# schematic.net
KiCad netlist of a schematic drawn in Altium Designer
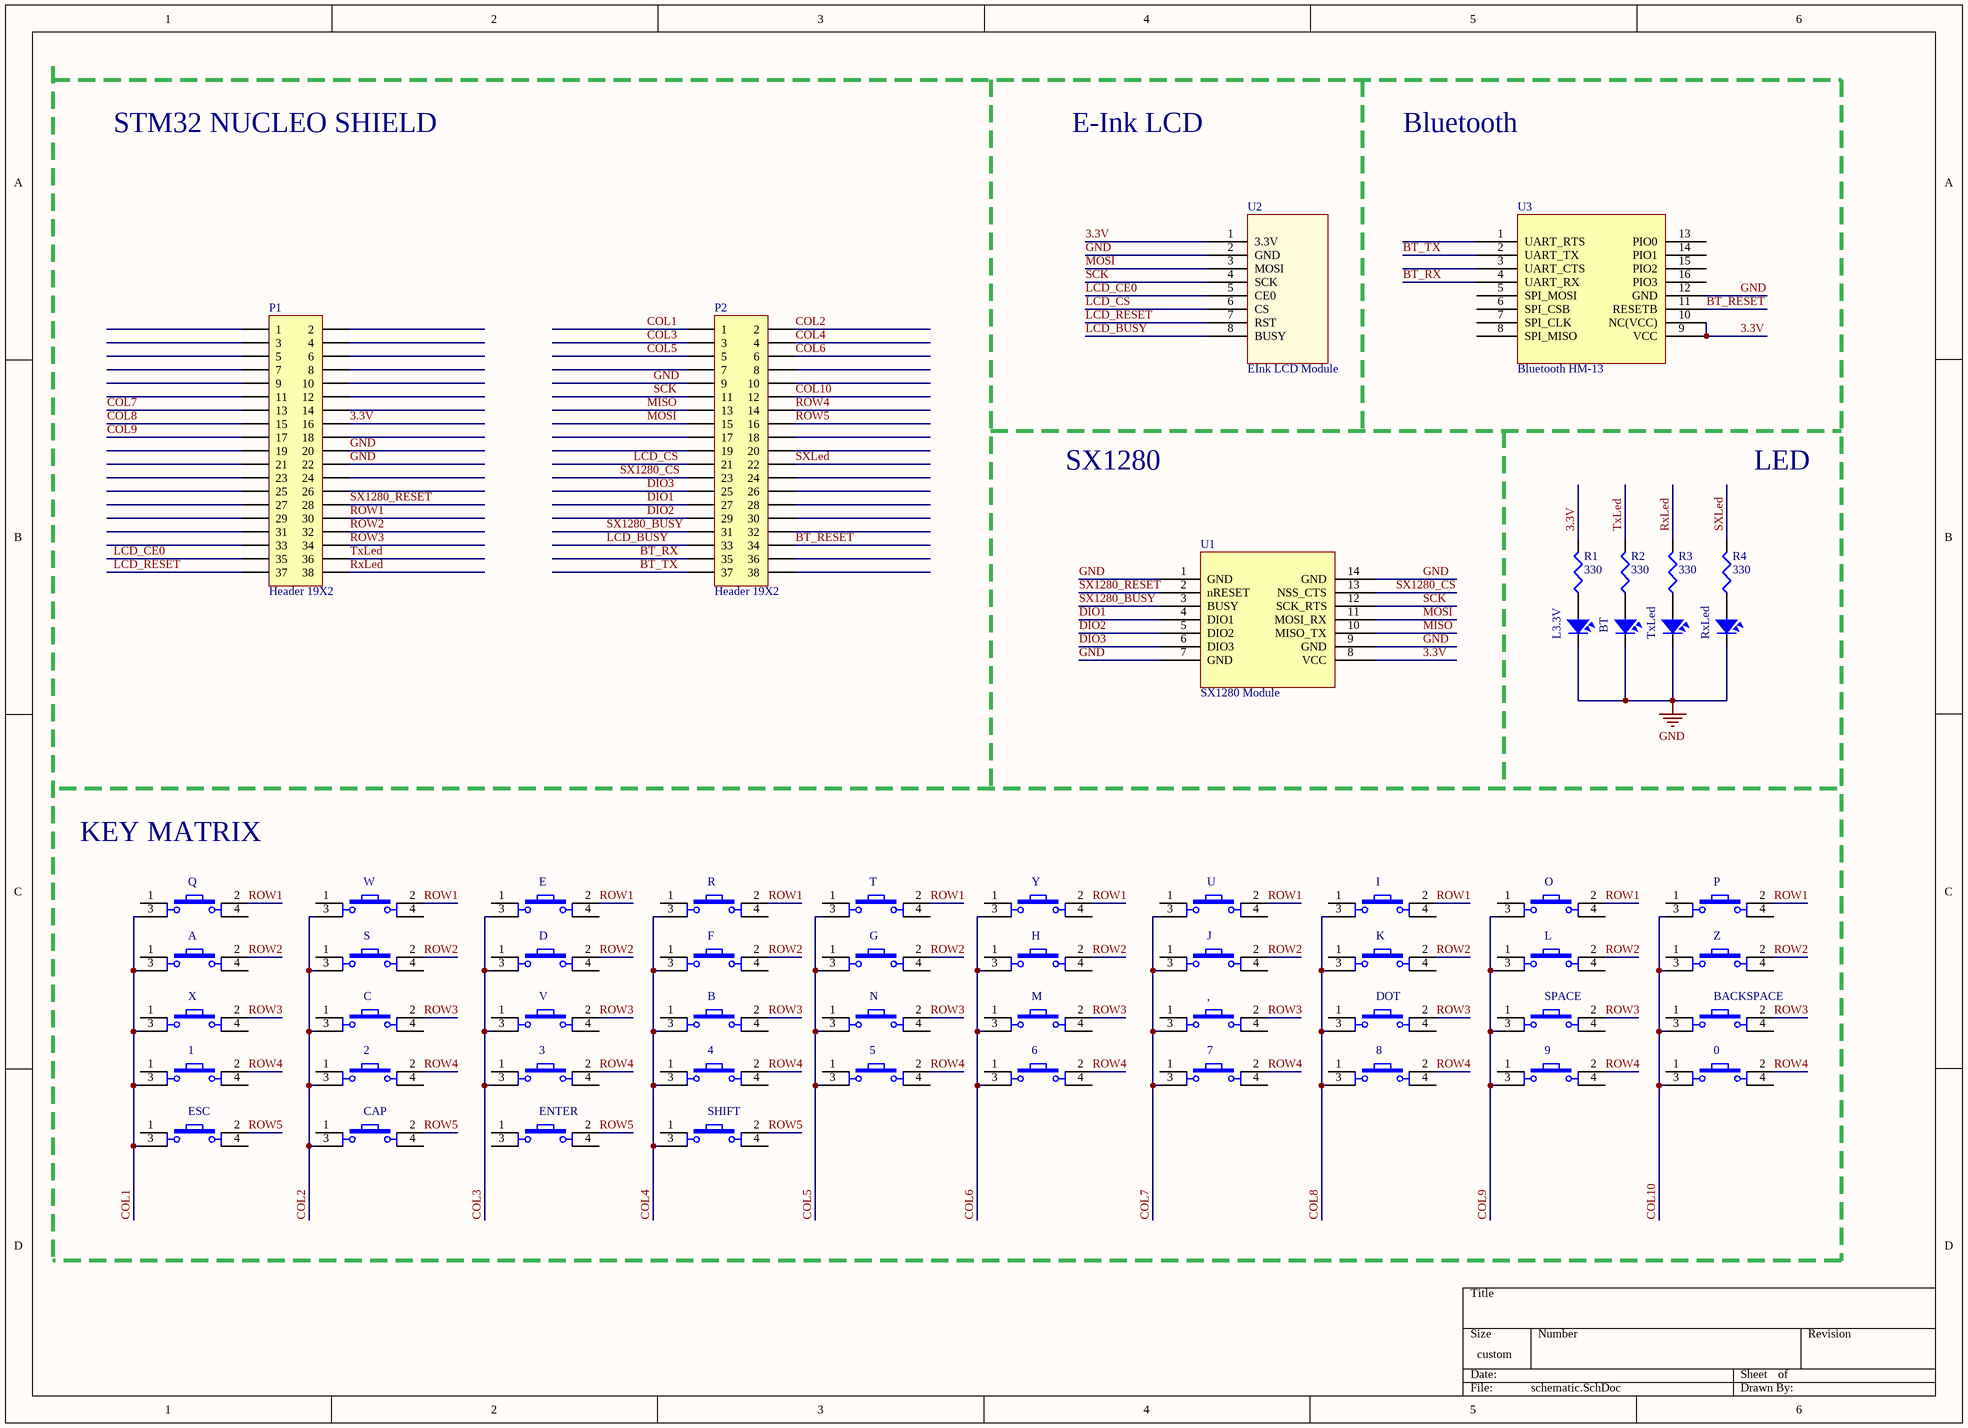
[diagram p0: schematic.SchDoc]

(export (version "E")
  (design (tool "Eeschema 10.0.6"))
  (components
    (comp (ref ",")
      (value "SW")
      (footprint "Button 4 pins")
      (description "Switch button 4 pin")
      (libsource (lib "syhaunguyen") (part "SW4"))
    )
    (comp (ref "0")
      (value "SW")
      (footprint "Button 4 pins")
      (description "Switch button 4 pin")
      (libsource (lib "syhaunguyen") (part "SW4"))
    )
    (comp (ref "1")
      (value "SW")
      (footprint "Button 4 pins")
      (description "Switch button 4 pin")
      (libsource (lib "syhaunguyen") (part "SW4"))
    )
    (comp (ref "2")
      (value "SW")
      (footprint "Button 4 pins")
      (description "Switch button 4 pin")
      (libsource (lib "syhaunguyen") (part "SW4"))
    )
    (comp (ref "3")
      (value "SW")
      (footprint "Button 4 pins")
      (description "Switch button 4 pin")
      (libsource (lib "syhaunguyen") (part "SW4"))
    )
    (comp (ref "4")
      (value "SW")
      (footprint "Button 4 pins")
      (description "Switch button 4 pin")
      (libsource (lib "syhaunguyen") (part "SW4"))
    )
    (comp (ref "5")
      (value "SW")
      (footprint "Button 4 pins")
      (description "Switch button 4 pin")
      (libsource (lib "syhaunguyen") (part "SW4"))
    )
    (comp (ref "6")
      (value "SW")
      (footprint "Button 4 pins")
      (description "Switch button 4 pin")
      (libsource (lib "syhaunguyen") (part "SW4"))
    )
    (comp (ref "7")
      (value "SW")
      (footprint "Button 4 pins")
      (description "Switch button 4 pin")
      (libsource (lib "syhaunguyen") (part "SW4"))
    )
    (comp (ref "8")
      (value "SW")
      (footprint "Button 4 pins")
      (description "Switch button 4 pin")
      (libsource (lib "syhaunguyen") (part "SW4"))
    )
    (comp (ref "9")
      (value "SW")
      (footprint "Button 4 pins")
      (description "Switch button 4 pin")
      (libsource (lib "syhaunguyen") (part "SW4"))
    )
    (comp (ref "A")
      (value "SW")
      (footprint "Button 4 pins")
      (description "Switch button 4 pin")
      (libsource (lib "syhaunguyen") (part "SW4"))
    )
    (comp (ref "B")
      (value "SW")
      (footprint "Button 4 pins")
      (description "Switch button 4 pin")
      (libsource (lib "syhaunguyen") (part "SW4"))
    )
    (comp (ref "BACKSPACE")
      (value "SW")
      (footprint "Button 4 pins")
      (description "Switch button 4 pin")
      (libsource (lib "syhaunguyen") (part "SW4"))
    )
    (comp (ref "BT")
      (value "LED SMD")
      (footprint "SM-LED-0805-Blue")
      (libsource (lib "syhaunguyen") (part "LED-SMD-0805"))
    )
    (comp (ref "C")
      (value "SW")
      (footprint "Button 4 pins")
      (description "Switch button 4 pin")
      (libsource (lib "syhaunguyen") (part "SW4"))
    )
    (comp (ref "CAP")
      (value "SW")
      (footprint "Button 4 pins")
      (description "Switch button 4 pin")
      (libsource (lib "syhaunguyen") (part "SW4"))
    )
    (comp (ref "D")
      (value "SW")
      (footprint "Button 4 pins")
      (description "Switch button 4 pin")
      (libsource (lib "syhaunguyen") (part "SW4"))
    )
    (comp (ref "DOT")
      (value "SW")
      (footprint "Button 4 pins")
      (description "Switch button 4 pin")
      (libsource (lib "syhaunguyen") (part "SW4"))
    )
    (comp (ref "E")
      (value "SW")
      (footprint "Button 4 pins")
      (description "Switch button 4 pin")
      (libsource (lib "syhaunguyen") (part "SW4"))
    )
    (comp (ref "ENTER")
      (value "SW")
      (footprint "Button 4 pins")
      (description "Switch button 4 pin")
      (libsource (lib "syhaunguyen") (part "SW4"))
    )
    (comp (ref "ESC")
      (value "SW")
      (footprint "Button 4 pins")
      (description "Switch button 4 pin")
      (libsource (lib "syhaunguyen") (part "SW4"))
    )
    (comp (ref "F")
      (value "SW")
      (footprint "Button 4 pins")
      (description "Switch button 4 pin")
      (libsource (lib "syhaunguyen") (part "SW4"))
    )
    (comp (ref "G")
      (value "SW")
      (footprint "Button 4 pins")
      (description "Switch button 4 pin")
      (libsource (lib "syhaunguyen") (part "SW4"))
    )
    (comp (ref "H")
      (value "SW")
      (footprint "Button 4 pins")
      (description "Switch button 4 pin")
      (libsource (lib "syhaunguyen") (part "SW4"))
    )
    (comp (ref "I")
      (value "SW")
      (footprint "Button 4 pins")
      (description "Switch button 4 pin")
      (libsource (lib "syhaunguyen") (part "SW4"))
    )
    (comp (ref "J")
      (value "SW")
      (footprint "Button 4 pins")
      (description "Switch button 4 pin")
      (libsource (lib "syhaunguyen") (part "SW4"))
    )
    (comp (ref "K")
      (value "SW")
      (footprint "Button 4 pins")
      (description "Switch button 4 pin")
      (libsource (lib "syhaunguyen") (part "SW4"))
    )
    (comp (ref "L")
      (value "SW")
      (footprint "Button 4 pins")
      (description "Switch button 4 pin")
      (libsource (lib "syhaunguyen") (part "SW4"))
    )
    (comp (ref "L3.3V")
      (value "LED SMD")
      (footprint "SM-LED-0805-Blue")
      (libsource (lib "syhaunguyen") (part "LED-SMD-0805"))
    )
    (comp (ref "M")
      (value "SW")
      (footprint "Button 4 pins")
      (description "Switch button 4 pin")
      (libsource (lib "syhaunguyen") (part "SW4"))
    )
    (comp (ref "N")
      (value "SW")
      (footprint "Button 4 pins")
      (description "Switch button 4 pin")
      (libsource (lib "syhaunguyen") (part "SW4"))
    )
    (comp (ref "O")
      (value "SW")
      (footprint "Button 4 pins")
      (description "Switch button 4 pin")
      (libsource (lib "syhaunguyen") (part "SW4"))
    )
    (comp (ref "P")
      (value "SW")
      (footprint "Button 4 pins")
      (description "Switch button 4 pin")
      (libsource (lib "syhaunguyen") (part "SW4"))
    )
    (comp (ref "P1")
      (value "Header 19X2")
      (footprint "HDR2X19")
      (description "Header, 19-Pin, Dual row")
      (fields (field (name "PUBLISHER") "Altium Limited"))
      (libsource (lib "Miscellaneous Connectors") (part "Header 19X2"))
    )
    (comp (ref "P2")
      (value "Header 19X2")
      (footprint "HDR2X19")
      (description "Header, 19-Pin, Dual row")
      (fields (field (name "PUBLISHER") "Altium Limited"))
      (libsource (lib "Miscellaneous Connectors") (part "Header 19X2"))
    )
    (comp (ref "Q")
      (value "SW")
      (footprint "Button 4 pins")
      (description "Switch button 4 pin")
      (libsource (lib "syhaunguyen") (part "SW4"))
    )
    (comp (ref "R")
      (value "SW")
      (footprint "Button 4 pins")
      (description "Switch button 4 pin")
      (libsource (lib "syhaunguyen") (part "SW4"))
    )
    (comp (ref "R1")
      (value "330")
      (footprint "J1-0603")
      (description "Resistor")
      (fields (field (name "Comment") "Res3") (field (name "PUBLISHER") "Altium Limited"))
      (libsource (lib "Miscellaneous Devices") (part "Res3"))
    )
    (comp (ref "R2")
      (value "330")
      (footprint "J1-0603")
      (description "Resistor")
      (fields (field (name "Comment") "Res3") (field (name "PUBLISHER") "Altium Limited"))
      (libsource (lib "Miscellaneous Devices") (part "Res3"))
    )
    (comp (ref "R3")
      (value "330")
      (footprint "J1-0603")
      (description "Resistor")
      (fields (field (name "Comment") "Res3") (field (name "PUBLISHER") "Altium Limited"))
      (libsource (lib "Miscellaneous Devices") (part "Res3"))
    )
    (comp (ref "R4")
      (value "330")
      (footprint "J1-0603")
      (description "Resistor")
      (fields (field (name "Comment") "Res3") (field (name "PUBLISHER") "Altium Limited"))
      (libsource (lib "Miscellaneous Devices") (part "Res3"))
    )
    (comp (ref "RxLed")
      (value "LED SMD")
      (footprint "SM-LED-0805-Blue")
      (libsource (lib "syhaunguyen") (part "LED-SMD-0805"))
    )
    (comp (ref "S")
      (value "SW")
      (footprint "Button 4 pins")
      (description "Switch button 4 pin")
      (libsource (lib "syhaunguyen") (part "SW4"))
    )
    (comp (ref "SHIFT")
      (value "SW")
      (footprint "Button 4 pins")
      (description "Switch button 4 pin")
      (libsource (lib "syhaunguyen") (part "SW4"))
    )
    (comp (ref "SPACE")
      (value "SW")
      (footprint "Button 4 pins")
      (description "Switch button 4 pin")
      (libsource (lib "syhaunguyen") (part "SW4"))
    )
    (comp (ref "T")
      (value "SW")
      (footprint "Button 4 pins")
      (description "Switch button 4 pin")
      (libsource (lib "syhaunguyen") (part "SW4"))
    )
    (comp (ref "TxLed")
      (value "LED SMD")
      (footprint "SM-LED-0805-Blue")
      (libsource (lib "syhaunguyen") (part "LED-SMD-0805"))
    )
    (comp (ref "U")
      (value "SW")
      (footprint "Button 4 pins")
      (description "Switch button 4 pin")
      (libsource (lib "syhaunguyen") (part "SW4"))
    )
    (comp (ref "U1")
      (value "SX1280 Module")
      (footprint "SX1280 Module")
      (libsource (lib "EInk_Project_Lib") (part "SX1280 Module"))
    )
    (comp (ref "U2")
      (value "EInk LCD Module")
      (footprint "EInk_Module")
      (libsource (lib "EInk_Project_Lib") (part "E-Ink LCD"))
    )
    (comp (ref "U3")
      (value "Bluetooth HM-13")
      (footprint "Bluetooth HM-13")
      (libsource (lib "EInk_Project_Lib") (part "Bluetooth HM-13"))
    )
    (comp (ref "V")
      (value "SW")
      (footprint "Button 4 pins")
      (description "Switch button 4 pin")
      (libsource (lib "syhaunguyen") (part "SW4"))
    )
    (comp (ref "W")
      (value "SW")
      (footprint "Button 4 pins")
      (description "Switch button 4 pin")
      (libsource (lib "syhaunguyen") (part "SW4"))
    )
    (comp (ref "X")
      (value "SW")
      (footprint "Button 4 pins")
      (description "Switch button 4 pin")
      (libsource (lib "syhaunguyen") (part "SW4"))
    )
    (comp (ref "Y")
      (value "SW")
      (footprint "Button 4 pins")
      (description "Switch button 4 pin")
      (libsource (lib "syhaunguyen") (part "SW4"))
    )
    (comp (ref "Z")
      (value "SW")
      (footprint "Button 4 pins")
      (description "Switch button 4 pin")
      (libsource (lib "syhaunguyen") (part "SW4"))
    )
  )
  (nets
    (net (code "1") (name "/3.3V") (class "Default")
      (node (ref "P1") (pin "16") (pinfunction "16_16") (pintype "passive"))
      (node (ref "R1") (pin "2") (pinfunction "2_2") (pintype "passive"))
      (node (ref "U1") (pin "8") (pinfunction "VCC_8") (pintype "passive"))
      (node (ref "U2") (pin "1") (pinfunction "3.3V_1") (pintype "passive"))
      (node (ref "U3") (pin "10") (pinfunction "NC(VCC)_10") (pintype "passive"))
      (node (ref "U3") (pin "9") (pinfunction "VCC_9") (pintype "passive"))
    )
    (net (code "2") (name "/BT_RESET") (class "Default")
      (node (ref "P2") (pin "34") (pinfunction "34_34") (pintype "passive"))
      (node (ref "U3") (pin "11") (pinfunction "RESETB_11") (pintype "passive"))
    )
    (net (code "3") (name "/BT_RX") (class "Default")
      (node (ref "P2") (pin "35") (pinfunction "35_35") (pintype "passive"))
      (node (ref "U3") (pin "4") (pinfunction "UART_RX_4") (pintype "passive"))
    )
    (net (code "4") (name "/BT_TX") (class "Default")
      (node (ref "P2") (pin "37") (pinfunction "37_37") (pintype "passive"))
      (node (ref "U3") (pin "2") (pinfunction "UART_TX_2") (pintype "passive"))
    )
    (net (code "5") (name "/COL1") (class "Default")
      (node (ref "1") (pin "3") (pintype "passive"))
      (node (ref "A") (pin "3") (pintype "passive"))
      (node (ref "ESC") (pin "3") (pintype "passive"))
      (node (ref "P2") (pin "1") (pinfunction "1_1") (pintype "passive"))
      (node (ref "Q") (pin "3") (pintype "passive"))
      (node (ref "X") (pin "3") (pintype "passive"))
    )
    (net (code "6") (name "/COL2") (class "Default")
      (node (ref "2") (pin "3") (pintype "passive"))
      (node (ref "C") (pin "3") (pintype "passive"))
      (node (ref "CAP") (pin "3") (pintype "passive"))
      (node (ref "P2") (pin "2") (pinfunction "2_2") (pintype "passive"))
      (node (ref "S") (pin "3") (pintype "passive"))
      (node (ref "W") (pin "3") (pintype "passive"))
    )
    (net (code "7") (name "/COL3") (class "Default")
      (node (ref "3") (pin "3") (pintype "passive"))
      (node (ref "D") (pin "3") (pintype "passive"))
      (node (ref "E") (pin "3") (pintype "passive"))
      (node (ref "P2") (pin "3") (pinfunction "3_3") (pintype "passive"))
      (node (ref "V") (pin "3") (pintype "passive"))
    )
    (net (code "8") (name "/COL4") (class "Default")
      (node (ref "4") (pin "3") (pintype "passive"))
      (node (ref "B") (pin "3") (pintype "passive"))
      (node (ref "F") (pin "3") (pintype "passive"))
      (node (ref "P2") (pin "4") (pinfunction "4_4") (pintype "passive"))
      (node (ref "R") (pin "3") (pintype "passive"))
      (node (ref "SHIFT") (pin "3") (pintype "passive"))
    )
    (net (code "9") (name "/COL5") (class "Default")
      (node (ref "5") (pin "3") (pintype "passive"))
      (node (ref "G") (pin "3") (pintype "passive"))
      (node (ref "N") (pin "3") (pintype "passive"))
      (node (ref "P2") (pin "5") (pinfunction "5_5") (pintype "passive"))
      (node (ref "T") (pin "3") (pintype "passive"))
    )
    (net (code "10") (name "/COL6") (class "Default")
      (node (ref "6") (pin "3") (pintype "passive"))
      (node (ref "H") (pin "3") (pintype "passive"))
      (node (ref "M") (pin "3") (pintype "passive"))
      (node (ref "P2") (pin "6") (pinfunction "6_6") (pintype "passive"))
      (node (ref "Y") (pin "3") (pintype "passive"))
    )
    (net (code "11") (name "/COL7") (class "Default")
      (node (ref ",") (pin "3") (pintype "passive"))
      (node (ref "7") (pin "3") (pintype "passive"))
      (node (ref "J") (pin "3") (pintype "passive"))
      (node (ref "P1") (pin "13") (pinfunction "13_13") (pintype "passive"))
      (node (ref "U") (pin "3") (pintype "passive"))
    )
    (net (code "12") (name "/COL8") (class "Default")
      (node (ref "8") (pin "3") (pintype "passive"))
      (node (ref "DOT") (pin "3") (pintype "passive"))
      (node (ref "I") (pin "3") (pintype "passive"))
      (node (ref "K") (pin "3") (pintype "passive"))
      (node (ref "P1") (pin "15") (pinfunction "15_15") (pintype "passive"))
    )
    (net (code "13") (name "/COL9") (class "Default")
      (node (ref "9") (pin "3") (pintype "passive"))
      (node (ref "L") (pin "3") (pintype "passive"))
      (node (ref "O") (pin "3") (pintype "passive"))
      (node (ref "P1") (pin "17") (pinfunction "17_17") (pintype "passive"))
      (node (ref "SPACE") (pin "3") (pintype "passive"))
    )
    (net (code "14") (name "/COL10") (class "Default")
      (node (ref "0") (pin "3") (pintype "passive"))
      (node (ref "BACKSPACE") (pin "3") (pintype "passive"))
      (node (ref "P") (pin "3") (pintype "passive"))
      (node (ref "P2") (pin "12") (pinfunction "12_12") (pintype "passive"))
      (node (ref "Z") (pin "3") (pintype "passive"))
    )
    (net (code "15") (name "/DIO1") (class "Default")
      (node (ref "P2") (pin "27") (pinfunction "27_27") (pintype "passive"))
      (node (ref "U1") (pin "4") (pinfunction "DIO1_4") (pintype "passive"))
    )
    (net (code "16") (name "/DIO2") (class "Default")
      (node (ref "P2") (pin "29") (pinfunction "29_29") (pintype "passive"))
      (node (ref "U1") (pin "5") (pinfunction "DIO2_5") (pintype "passive"))
    )
    (net (code "17") (name "/DIO3") (class "Default")
      (node (ref "P2") (pin "25") (pinfunction "25_25") (pintype "passive"))
      (node (ref "U1") (pin "6") (pinfunction "DIO3_6") (pintype "passive"))
    )
    (net (code "18") (name "/LCD_BUSY") (class "Default")
      (node (ref "P2") (pin "33") (pinfunction "33_33") (pintype "passive"))
      (node (ref "U2") (pin "8") (pinfunction "BUSY_8") (pintype "passive"))
    )
    (net (code "19") (name "/LCD_CE0") (class "Default")
      (node (ref "P1") (pin "35") (pinfunction "35_35") (pintype "passive"))
      (node (ref "U2") (pin "5") (pinfunction "CE0_5") (pintype "passive"))
    )
    (net (code "20") (name "/LCD_CS") (class "Default")
      (node (ref "P2") (pin "21") (pinfunction "21_21") (pintype "passive"))
      (node (ref "U2") (pin "6") (pinfunction "CS_6") (pintype "passive"))
    )
    (net (code "21") (name "/LCD_RESET") (class "Default")
      (node (ref "P1") (pin "37") (pinfunction "37_37") (pintype "passive"))
      (node (ref "U2") (pin "7") (pinfunction "RST_7") (pintype "passive"))
    )
    (net (code "22") (name "/MISO") (class "Default")
      (node (ref "P2") (pin "13") (pinfunction "13_13") (pintype "passive"))
      (node (ref "U1") (pin "10") (pinfunction "MISO_TX_10") (pintype "passive"))
    )
    (net (code "23") (name "/MOSI") (class "Default")
      (node (ref "P2") (pin "15") (pinfunction "15_15") (pintype "passive"))
      (node (ref "U1") (pin "11") (pinfunction "MOSI_RX_11") (pintype "passive"))
      (node (ref "U2") (pin "3") (pinfunction "MOSI_3") (pintype "passive"))
    )
    (net (code "24") (name "/ROW1") (class "Default")
      (node (ref "E") (pin "2") (pintype "passive"))
      (node (ref "I") (pin "2") (pintype "passive"))
      (node (ref "O") (pin "2") (pintype "passive"))
      (node (ref "P") (pin "2") (pintype "passive"))
      (node (ref "P1") (pin "30") (pinfunction "30_30") (pintype "passive"))
      (node (ref "Q") (pin "2") (pintype "passive"))
      (node (ref "R") (pin "2") (pintype "passive"))
      (node (ref "T") (pin "2") (pintype "passive"))
      (node (ref "U") (pin "2") (pintype "passive"))
      (node (ref "W") (pin "2") (pintype "passive"))
      (node (ref "Y") (pin "2") (pintype "passive"))
    )
    (net (code "25") (name "/ROW2") (class "Default")
      (node (ref "A") (pin "2") (pintype "passive"))
      (node (ref "D") (pin "2") (pintype "passive"))
      (node (ref "F") (pin "2") (pintype "passive"))
      (node (ref "G") (pin "2") (pintype "passive"))
      (node (ref "H") (pin "2") (pintype "passive"))
      (node (ref "J") (pin "2") (pintype "passive"))
      (node (ref "K") (pin "2") (pintype "passive"))
      (node (ref "L") (pin "2") (pintype "passive"))
      (node (ref "P1") (pin "32") (pinfunction "32_32") (pintype "passive"))
      (node (ref "S") (pin "2") (pintype "passive"))
      (node (ref "Z") (pin "2") (pintype "passive"))
    )
    (net (code "26") (name "/ROW3") (class "Default")
      (node (ref ",") (pin "2") (pintype "passive"))
      (node (ref "B") (pin "2") (pintype "passive"))
      (node (ref "BACKSPACE") (pin "2") (pintype "passive"))
      (node (ref "C") (pin "2") (pintype "passive"))
      (node (ref "DOT") (pin "2") (pintype "passive"))
      (node (ref "M") (pin "2") (pintype "passive"))
      (node (ref "N") (pin "2") (pintype "passive"))
      (node (ref "P1") (pin "34") (pinfunction "34_34") (pintype "passive"))
      (node (ref "SPACE") (pin "2") (pintype "passive"))
      (node (ref "V") (pin "2") (pintype "passive"))
      (node (ref "X") (pin "2") (pintype "passive"))
    )
    (net (code "27") (name "/ROW4") (class "Default")
      (node (ref "0") (pin "2") (pintype "passive"))
      (node (ref "1") (pin "2") (pintype "passive"))
      (node (ref "2") (pin "2") (pintype "passive"))
      (node (ref "3") (pin "2") (pintype "passive"))
      (node (ref "4") (pin "2") (pintype "passive"))
      (node (ref "5") (pin "2") (pintype "passive"))
      (node (ref "6") (pin "2") (pintype "passive"))
      (node (ref "7") (pin "2") (pintype "passive"))
      (node (ref "8") (pin "2") (pintype "passive"))
      (node (ref "9") (pin "2") (pintype "passive"))
      (node (ref "P2") (pin "14") (pinfunction "14_14") (pintype "passive"))
    )
    (net (code "28") (name "/ROW5") (class "Default")
      (node (ref "CAP") (pin "2") (pintype "passive"))
      (node (ref "ENTER") (pin "2") (pintype "passive"))
      (node (ref "ESC") (pin "2") (pintype "passive"))
      (node (ref "P2") (pin "16") (pinfunction "16_16") (pintype "passive"))
      (node (ref "SHIFT") (pin "2") (pintype "passive"))
    )
    (net (code "29") (name "/RxLed") (class "Default")
      (node (ref "P1") (pin "38") (pinfunction "38_38") (pintype "passive"))
      (node (ref "R3") (pin "2") (pinfunction "2_2") (pintype "passive"))
    )
    (net (code "30") (name "/SCK") (class "Default")
      (node (ref "P2") (pin "11") (pinfunction "11_11") (pintype "passive"))
      (node (ref "U1") (pin "12") (pinfunction "SCK_RTS_12") (pintype "passive"))
      (node (ref "U2") (pin "4") (pinfunction "SCK_4") (pintype "passive"))
    )
    (net (code "31") (name "/SX1280_BUSY") (class "Default")
      (node (ref "P2") (pin "31") (pinfunction "31_31") (pintype "passive"))
      (node (ref "U1") (pin "3") (pinfunction "BUSY_3") (pintype "passive"))
    )
    (net (code "32") (name "/SX1280_CS") (class "Default")
      (node (ref "P2") (pin "23") (pinfunction "23_23") (pintype "passive"))
      (node (ref "U1") (pin "13") (pinfunction "NSS_CTS_13") (pintype "passive"))
    )
    (net (code "33") (name "/SX1280_RESET") (class "Default")
      (node (ref "P1") (pin "28") (pinfunction "28_28") (pintype "passive"))
      (node (ref "U1") (pin "2") (pinfunction "nRESET_2") (pintype "passive"))
    )
    (net (code "34") (name "/SXLed") (class "Default")
      (node (ref "P2") (pin "22") (pinfunction "22_22") (pintype "passive"))
      (node (ref "R4") (pin "2") (pinfunction "2_2") (pintype "passive"))
    )
    (net (code "35") (name "/TxLed") (class "Default")
      (node (ref "P1") (pin "36") (pinfunction "36_36") (pintype "passive"))
      (node (ref "R2") (pin "2") (pinfunction "2_2") (pintype "passive"))
    )
    (net (code "36") (name "GND") (class "Default")
      (node (ref "BT") (pin "2") (pinfunction "2_2") (pintype "passive"))
      (node (ref "L3.3V") (pin "2") (pinfunction "2_2") (pintype "passive"))
      (node (ref "P1") (pin "20") (pinfunction "20_20") (pintype "passive"))
      (node (ref "P1") (pin "22") (pinfunction "22_22") (pintype "passive"))
      (node (ref "P2") (pin "9") (pinfunction "9_9") (pintype "passive"))
      (node (ref "RxLed") (pin "2") (pinfunction "2_2") (pintype "passive"))
      (node (ref "TxLed") (pin "2") (pinfunction "2_2") (pintype "passive"))
      (node (ref "U1") (pin "1") (pinfunction "GND_1") (pintype "passive"))
      (node (ref "U1") (pin "14") (pinfunction "GND_14") (pintype "passive"))
      (node (ref "U1") (pin "7") (pinfunction "GND_7") (pintype "passive"))
      (node (ref "U1") (pin "9") (pinfunction "GND_9") (pintype "passive"))
      (node (ref "U2") (pin "2") (pinfunction "GND_2") (pintype "passive"))
      (node (ref "U3") (pin "12") (pinfunction "GND_12") (pintype "passive"))
    )
    (net (code "37") (name "Net-(BT-Pad1)") (class "Default")
      (node (ref "BT") (pin "1") (pinfunction "1_1") (pintype "passive"))
      (node (ref "R2") (pin "1") (pinfunction "1_1") (pintype "passive"))
    )
    (net (code "38") (name "Net-(L3.3V-Pad1)") (class "Default")
      (node (ref "L3.3V") (pin "1") (pinfunction "1_1") (pintype "passive"))
      (node (ref "R1") (pin "1") (pinfunction "1_1") (pintype "passive"))
    )
    (net (code "39") (name "Net-(R3-Pad1)") (class "Default")
      (node (ref "R3") (pin "1") (pinfunction "1_1") (pintype "passive"))
      (node (ref "TxLed") (pin "1") (pinfunction "1_1") (pintype "passive"))
    )
    (net (code "40") (name "Net-(R4-Pad1)") (class "Default")
      (node (ref "R4") (pin "1") (pinfunction "1_1") (pintype "passive"))
      (node (ref "RxLed") (pin "1") (pinfunction "1_1") (pintype "passive"))
    )
    (net (code "41") (name "unconnected-(,-Pad1)") (class "Default")
      (node (ref ",") (pin "1") (pintype "passive"))
    )
    (net (code "42") (name "unconnected-(,-Pad4)") (class "Default")
      (node (ref ",") (pin "4") (pintype "passive"))
    )
    (net (code "43") (name "unconnected-(0-Pad1)") (class "Default")
      (node (ref "0") (pin "1") (pintype "passive"))
    )
    (net (code "44") (name "unconnected-(0-Pad4)") (class "Default")
      (node (ref "0") (pin "4") (pintype "passive"))
    )
    (net (code "45") (name "unconnected-(1-Pad1)") (class "Default")
      (node (ref "1") (pin "1") (pintype "passive"))
    )
    (net (code "46") (name "unconnected-(1-Pad4)") (class "Default")
      (node (ref "1") (pin "4") (pintype "passive"))
    )
    (net (code "47") (name "unconnected-(2-Pad1)") (class "Default")
      (node (ref "2") (pin "1") (pintype "passive"))
    )
    (net (code "48") (name "unconnected-(2-Pad4)") (class "Default")
      (node (ref "2") (pin "4") (pintype "passive"))
    )
    (net (code "49") (name "unconnected-(3-Pad1)") (class "Default")
      (node (ref "3") (pin "1") (pintype "passive"))
    )
    (net (code "50") (name "unconnected-(3-Pad4)") (class "Default")
      (node (ref "3") (pin "4") (pintype "passive"))
    )
    (net (code "51") (name "unconnected-(4-Pad1)") (class "Default")
      (node (ref "4") (pin "1") (pintype "passive"))
    )
    (net (code "52") (name "unconnected-(4-Pad4)") (class "Default")
      (node (ref "4") (pin "4") (pintype "passive"))
    )
    (net (code "53") (name "unconnected-(5-Pad1)") (class "Default")
      (node (ref "5") (pin "1") (pintype "passive"))
    )
    (net (code "54") (name "unconnected-(5-Pad4)") (class "Default")
      (node (ref "5") (pin "4") (pintype "passive"))
    )
    (net (code "55") (name "unconnected-(6-Pad1)") (class "Default")
      (node (ref "6") (pin "1") (pintype "passive"))
    )
    (net (code "56") (name "unconnected-(6-Pad4)") (class "Default")
      (node (ref "6") (pin "4") (pintype "passive"))
    )
    (net (code "57") (name "unconnected-(7-Pad1)") (class "Default")
      (node (ref "7") (pin "1") (pintype "passive"))
    )
    (net (code "58") (name "unconnected-(7-Pad4)") (class "Default")
      (node (ref "7") (pin "4") (pintype "passive"))
    )
    (net (code "59") (name "unconnected-(8-Pad1)") (class "Default")
      (node (ref "8") (pin "1") (pintype "passive"))
    )
    (net (code "60") (name "unconnected-(8-Pad4)") (class "Default")
      (node (ref "8") (pin "4") (pintype "passive"))
    )
    (net (code "61") (name "unconnected-(9-Pad1)") (class "Default")
      (node (ref "9") (pin "1") (pintype "passive"))
    )
    (net (code "62") (name "unconnected-(9-Pad4)") (class "Default")
      (node (ref "9") (pin "4") (pintype "passive"))
    )
    (net (code "63") (name "unconnected-(A-Pad1)") (class "Default")
      (node (ref "A") (pin "1") (pintype "passive"))
    )
    (net (code "64") (name "unconnected-(A-Pad4)") (class "Default")
      (node (ref "A") (pin "4") (pintype "passive"))
    )
    (net (code "65") (name "unconnected-(B-Pad1)") (class "Default")
      (node (ref "B") (pin "1") (pintype "passive"))
    )
    (net (code "66") (name "unconnected-(B-Pad4)") (class "Default")
      (node (ref "B") (pin "4") (pintype "passive"))
    )
    (net (code "67") (name "unconnected-(BACKSPACE-Pad1)") (class "Default")
      (node (ref "BACKSPACE") (pin "1") (pintype "passive"))
    )
    (net (code "68") (name "unconnected-(BACKSPACE-Pad4)") (class "Default")
      (node (ref "BACKSPACE") (pin "4") (pintype "passive"))
    )
    (net (code "69") (name "unconnected-(C-Pad1)") (class "Default")
      (node (ref "C") (pin "1") (pintype "passive"))
    )
    (net (code "70") (name "unconnected-(C-Pad4)") (class "Default")
      (node (ref "C") (pin "4") (pintype "passive"))
    )
    (net (code "71") (name "unconnected-(CAP-Pad1)") (class "Default")
      (node (ref "CAP") (pin "1") (pintype "passive"))
    )
    (net (code "72") (name "unconnected-(CAP-Pad4)") (class "Default")
      (node (ref "CAP") (pin "4") (pintype "passive"))
    )
    (net (code "73") (name "unconnected-(D-Pad1)") (class "Default")
      (node (ref "D") (pin "1") (pintype "passive"))
    )
    (net (code "74") (name "unconnected-(D-Pad4)") (class "Default")
      (node (ref "D") (pin "4") (pintype "passive"))
    )
    (net (code "75") (name "unconnected-(DOT-Pad1)") (class "Default")
      (node (ref "DOT") (pin "1") (pintype "passive"))
    )
    (net (code "76") (name "unconnected-(DOT-Pad4)") (class "Default")
      (node (ref "DOT") (pin "4") (pintype "passive"))
    )
    (net (code "77") (name "unconnected-(E-Pad1)") (class "Default")
      (node (ref "E") (pin "1") (pintype "passive"))
    )
    (net (code "78") (name "unconnected-(E-Pad4)") (class "Default")
      (node (ref "E") (pin "4") (pintype "passive"))
    )
    (net (code "79") (name "unconnected-(ENTER-Pad1)") (class "Default")
      (node (ref "ENTER") (pin "1") (pintype "passive"))
    )
    (net (code "80") (name "unconnected-(ENTER-Pad3)") (class "Default")
      (node (ref "ENTER") (pin "3") (pintype "passive"))
    )
    (net (code "81") (name "unconnected-(ENTER-Pad4)") (class "Default")
      (node (ref "ENTER") (pin "4") (pintype "passive"))
    )
    (net (code "82") (name "unconnected-(ESC-Pad1)") (class "Default")
      (node (ref "ESC") (pin "1") (pintype "passive"))
    )
    (net (code "83") (name "unconnected-(ESC-Pad4)") (class "Default")
      (node (ref "ESC") (pin "4") (pintype "passive"))
    )
    (net (code "84") (name "unconnected-(F-Pad1)") (class "Default")
      (node (ref "F") (pin "1") (pintype "passive"))
    )
    (net (code "85") (name "unconnected-(F-Pad4)") (class "Default")
      (node (ref "F") (pin "4") (pintype "passive"))
    )
    (net (code "86") (name "unconnected-(G-Pad1)") (class "Default")
      (node (ref "G") (pin "1") (pintype "passive"))
    )
    (net (code "87") (name "unconnected-(G-Pad4)") (class "Default")
      (node (ref "G") (pin "4") (pintype "passive"))
    )
    (net (code "88") (name "unconnected-(H-Pad1)") (class "Default")
      (node (ref "H") (pin "1") (pintype "passive"))
    )
    (net (code "89") (name "unconnected-(H-Pad4)") (class "Default")
      (node (ref "H") (pin "4") (pintype "passive"))
    )
    (net (code "90") (name "unconnected-(I-Pad1)") (class "Default")
      (node (ref "I") (pin "1") (pintype "passive"))
    )
    (net (code "91") (name "unconnected-(I-Pad4)") (class "Default")
      (node (ref "I") (pin "4") (pintype "passive"))
    )
    (net (code "92") (name "unconnected-(J-Pad1)") (class "Default")
      (node (ref "J") (pin "1") (pintype "passive"))
    )
    (net (code "93") (name "unconnected-(J-Pad4)") (class "Default")
      (node (ref "J") (pin "4") (pintype "passive"))
    )
    (net (code "94") (name "unconnected-(K-Pad1)") (class "Default")
      (node (ref "K") (pin "1") (pintype "passive"))
    )
    (net (code "95") (name "unconnected-(K-Pad4)") (class "Default")
      (node (ref "K") (pin "4") (pintype "passive"))
    )
    (net (code "96") (name "unconnected-(L-Pad1)") (class "Default")
      (node (ref "L") (pin "1") (pintype "passive"))
    )
    (net (code "97") (name "unconnected-(L-Pad4)") (class "Default")
      (node (ref "L") (pin "4") (pintype "passive"))
    )
    (net (code "98") (name "unconnected-(M-Pad1)") (class "Default")
      (node (ref "M") (pin "1") (pintype "passive"))
    )
    (net (code "99") (name "unconnected-(M-Pad4)") (class "Default")
      (node (ref "M") (pin "4") (pintype "passive"))
    )
    (net (code "100") (name "unconnected-(N-Pad1)") (class "Default")
      (node (ref "N") (pin "1") (pintype "passive"))
    )
    (net (code "101") (name "unconnected-(N-Pad4)") (class "Default")
      (node (ref "N") (pin "4") (pintype "passive"))
    )
    (net (code "102") (name "unconnected-(O-Pad1)") (class "Default")
      (node (ref "O") (pin "1") (pintype "passive"))
    )
    (net (code "103") (name "unconnected-(O-Pad4)") (class "Default")
      (node (ref "O") (pin "4") (pintype "passive"))
    )
    (net (code "104") (name "unconnected-(P-Pad1)") (class "Default")
      (node (ref "P") (pin "1") (pintype "passive"))
    )
    (net (code "105") (name "unconnected-(P-Pad4)") (class "Default")
      (node (ref "P") (pin "4") (pintype "passive"))
    )
    (net (code "106") (name "unconnected-(P1-Pad1)") (class "Default")
      (node (ref "P1") (pin "1") (pinfunction "1_1") (pintype "passive"))
    )
    (net (code "107") (name "unconnected-(P1-Pad2)") (class "Default")
      (node (ref "P1") (pin "2") (pinfunction "2_2") (pintype "passive"))
    )
    (net (code "108") (name "unconnected-(P1-Pad3)") (class "Default")
      (node (ref "P1") (pin "3") (pinfunction "3_3") (pintype "passive"))
    )
    (net (code "109") (name "unconnected-(P1-Pad4)") (class "Default")
      (node (ref "P1") (pin "4") (pinfunction "4_4") (pintype "passive"))
    )
    (net (code "110") (name "unconnected-(P1-Pad5)") (class "Default")
      (node (ref "P1") (pin "5") (pinfunction "5_5") (pintype "passive"))
    )
    (net (code "111") (name "unconnected-(P1-Pad6)") (class "Default")
      (node (ref "P1") (pin "6") (pinfunction "6_6") (pintype "passive"))
    )
    (net (code "112") (name "unconnected-(P1-Pad7)") (class "Default")
      (node (ref "P1") (pin "7") (pinfunction "7_7") (pintype "passive"))
    )
    (net (code "113") (name "unconnected-(P1-Pad8)") (class "Default")
      (node (ref "P1") (pin "8") (pinfunction "8_8") (pintype "passive"))
    )
    (net (code "114") (name "unconnected-(P1-Pad9)") (class "Default")
      (node (ref "P1") (pin "9") (pinfunction "9_9") (pintype "passive"))
    )
    (net (code "115") (name "unconnected-(P1-Pad10)") (class "Default")
      (node (ref "P1") (pin "10") (pinfunction "10_10") (pintype "passive"))
    )
    (net (code "116") (name "unconnected-(P1-Pad11)") (class "Default")
      (node (ref "P1") (pin "11") (pinfunction "11_11") (pintype "passive"))
    )
    (net (code "117") (name "unconnected-(P1-Pad12)") (class "Default")
      (node (ref "P1") (pin "12") (pinfunction "12_12") (pintype "passive"))
    )
    (net (code "118") (name "unconnected-(P1-Pad14)") (class "Default")
      (node (ref "P1") (pin "14") (pinfunction "14_14") (pintype "passive"))
    )
    (net (code "119") (name "unconnected-(P1-Pad18)") (class "Default")
      (node (ref "P1") (pin "18") (pinfunction "18_18") (pintype "passive"))
    )
    (net (code "120") (name "unconnected-(P1-Pad19)") (class "Default")
      (node (ref "P1") (pin "19") (pinfunction "19_19") (pintype "passive"))
    )
    (net (code "121") (name "unconnected-(P1-Pad21)") (class "Default")
      (node (ref "P1") (pin "21") (pinfunction "21_21") (pintype "passive"))
    )
    (net (code "122") (name "unconnected-(P1-Pad23)") (class "Default")
      (node (ref "P1") (pin "23") (pinfunction "23_23") (pintype "passive"))
    )
    (net (code "123") (name "unconnected-(P1-Pad24)") (class "Default")
      (node (ref "P1") (pin "24") (pinfunction "24_24") (pintype "passive"))
    )
    (net (code "124") (name "unconnected-(P1-Pad25)") (class "Default")
      (node (ref "P1") (pin "25") (pinfunction "25_25") (pintype "passive"))
    )
    (net (code "125") (name "unconnected-(P1-Pad26)") (class "Default")
      (node (ref "P1") (pin "26") (pinfunction "26_26") (pintype "passive"))
    )
    (net (code "126") (name "unconnected-(P1-Pad27)") (class "Default")
      (node (ref "P1") (pin "27") (pinfunction "27_27") (pintype "passive"))
    )
    (net (code "127") (name "unconnected-(P1-Pad29)") (class "Default")
      (node (ref "P1") (pin "29") (pinfunction "29_29") (pintype "passive"))
    )
    (net (code "128") (name "unconnected-(P1-Pad31)") (class "Default")
      (node (ref "P1") (pin "31") (pinfunction "31_31") (pintype "passive"))
    )
    (net (code "129") (name "unconnected-(P1-Pad33)") (class "Default")
      (node (ref "P1") (pin "33") (pinfunction "33_33") (pintype "passive"))
    )
    (net (code "130") (name "unconnected-(P2-Pad7)") (class "Default")
      (node (ref "P2") (pin "7") (pinfunction "7_7") (pintype "passive"))
    )
    (net (code "131") (name "unconnected-(P2-Pad8)") (class "Default")
      (node (ref "P2") (pin "8") (pinfunction "8_8") (pintype "passive"))
    )
    (net (code "132") (name "unconnected-(P2-Pad10)") (class "Default")
      (node (ref "P2") (pin "10") (pinfunction "10_10") (pintype "passive"))
    )
    (net (code "133") (name "unconnected-(P2-Pad17)") (class "Default")
      (node (ref "P2") (pin "17") (pinfunction "17_17") (pintype "passive"))
    )
    (net (code "134") (name "unconnected-(P2-Pad18)") (class "Default")
      (node (ref "P2") (pin "18") (pinfunction "18_18") (pintype "passive"))
    )
    (net (code "135") (name "unconnected-(P2-Pad19)") (class "Default")
      (node (ref "P2") (pin "19") (pinfunction "19_19") (pintype "passive"))
    )
    (net (code "136") (name "unconnected-(P2-Pad20)") (class "Default")
      (node (ref "P2") (pin "20") (pinfunction "20_20") (pintype "passive"))
    )
    (net (code "137") (name "unconnected-(P2-Pad24)") (class "Default")
      (node (ref "P2") (pin "24") (pinfunction "24_24") (pintype "passive"))
    )
    (net (code "138") (name "unconnected-(P2-Pad26)") (class "Default")
      (node (ref "P2") (pin "26") (pinfunction "26_26") (pintype "passive"))
    )
    (net (code "139") (name "unconnected-(P2-Pad28)") (class "Default")
      (node (ref "P2") (pin "28") (pinfunction "28_28") (pintype "passive"))
    )
    (net (code "140") (name "unconnected-(P2-Pad30)") (class "Default")
      (node (ref "P2") (pin "30") (pinfunction "30_30") (pintype "passive"))
    )
    (net (code "141") (name "unconnected-(P2-Pad32)") (class "Default")
      (node (ref "P2") (pin "32") (pinfunction "32_32") (pintype "passive"))
    )
    (net (code "142") (name "unconnected-(P2-Pad36)") (class "Default")
      (node (ref "P2") (pin "36") (pinfunction "36_36") (pintype "passive"))
    )
    (net (code "143") (name "unconnected-(P2-Pad38)") (class "Default")
      (node (ref "P2") (pin "38") (pinfunction "38_38") (pintype "passive"))
    )
    (net (code "144") (name "unconnected-(Q-Pad1)") (class "Default")
      (node (ref "Q") (pin "1") (pintype "passive"))
    )
    (net (code "145") (name "unconnected-(Q-Pad4)") (class "Default")
      (node (ref "Q") (pin "4") (pintype "passive"))
    )
    (net (code "146") (name "unconnected-(R-Pad1)") (class "Default")
      (node (ref "R") (pin "1") (pintype "passive"))
    )
    (net (code "147") (name "unconnected-(R-Pad4)") (class "Default")
      (node (ref "R") (pin "4") (pintype "passive"))
    )
    (net (code "148") (name "unconnected-(S-Pad1)") (class "Default")
      (node (ref "S") (pin "1") (pintype "passive"))
    )
    (net (code "149") (name "unconnected-(S-Pad4)") (class "Default")
      (node (ref "S") (pin "4") (pintype "passive"))
    )
    (net (code "150") (name "unconnected-(SHIFT-Pad1)") (class "Default")
      (node (ref "SHIFT") (pin "1") (pintype "passive"))
    )
    (net (code "151") (name "unconnected-(SHIFT-Pad4)") (class "Default")
      (node (ref "SHIFT") (pin "4") (pintype "passive"))
    )
    (net (code "152") (name "unconnected-(SPACE-Pad1)") (class "Default")
      (node (ref "SPACE") (pin "1") (pintype "passive"))
    )
    (net (code "153") (name "unconnected-(SPACE-Pad4)") (class "Default")
      (node (ref "SPACE") (pin "4") (pintype "passive"))
    )
    (net (code "154") (name "unconnected-(T-Pad1)") (class "Default")
      (node (ref "T") (pin "1") (pintype "passive"))
    )
    (net (code "155") (name "unconnected-(T-Pad4)") (class "Default")
      (node (ref "T") (pin "4") (pintype "passive"))
    )
    (net (code "156") (name "unconnected-(U-Pad1)") (class "Default")
      (node (ref "U") (pin "1") (pintype "passive"))
    )
    (net (code "157") (name "unconnected-(U-Pad4)") (class "Default")
      (node (ref "U") (pin "4") (pintype "passive"))
    )
    (net (code "158") (name "unconnected-(U3-PIO0-Pad13)") (class "Default")
      (node (ref "U3") (pin "13") (pinfunction "PIO0_13") (pintype "passive"))
    )
    (net (code "159") (name "unconnected-(U3-PIO1-Pad14)") (class "Default")
      (node (ref "U3") (pin "14") (pinfunction "PIO1_14") (pintype "passive"))
    )
    (net (code "160") (name "unconnected-(U3-PIO2-Pad15)") (class "Default")
      (node (ref "U3") (pin "15") (pinfunction "PIO2_15") (pintype "passive"))
    )
    (net (code "161") (name "unconnected-(U3-PIO3-Pad16)") (class "Default")
      (node (ref "U3") (pin "16") (pinfunction "PIO3_16") (pintype "passive"))
    )
    (net (code "162") (name "unconnected-(U3-SPI_CLK-Pad7)") (class "Default")
      (node (ref "U3") (pin "7") (pinfunction "SPI_CLK_7") (pintype "passive"))
    )
    (net (code "163") (name "unconnected-(U3-SPI_CSB-Pad6)") (class "Default")
      (node (ref "U3") (pin "6") (pinfunction "SPI_CSB_6") (pintype "passive"))
    )
    (net (code "164") (name "unconnected-(U3-SPI_MISO-Pad8)") (class "Default")
      (node (ref "U3") (pin "8") (pinfunction "SPI_MISO_8") (pintype "passive"))
    )
    (net (code "165") (name "unconnected-(U3-SPI_MOSI-Pad5)") (class "Default")
      (node (ref "U3") (pin "5") (pinfunction "SPI_MOSI_5") (pintype "passive"))
    )
    (net (code "166") (name "unconnected-(U3-UART_CTS-Pad3)") (class "Default")
      (node (ref "U3") (pin "3") (pinfunction "UART_CTS_3") (pintype "passive"))
    )
    (net (code "167") (name "unconnected-(U3-UART_RTS-Pad1)") (class "Default")
      (node (ref "U3") (pin "1") (pinfunction "UART_RTS_1") (pintype "passive"))
    )
    (net (code "168") (name "unconnected-(V-Pad1)") (class "Default")
      (node (ref "V") (pin "1") (pintype "passive"))
    )
    (net (code "169") (name "unconnected-(V-Pad4)") (class "Default")
      (node (ref "V") (pin "4") (pintype "passive"))
    )
    (net (code "170") (name "unconnected-(W-Pad1)") (class "Default")
      (node (ref "W") (pin "1") (pintype "passive"))
    )
    (net (code "171") (name "unconnected-(W-Pad4)") (class "Default")
      (node (ref "W") (pin "4") (pintype "passive"))
    )
    (net (code "172") (name "unconnected-(X-Pad1)") (class "Default")
      (node (ref "X") (pin "1") (pintype "passive"))
    )
    (net (code "173") (name "unconnected-(X-Pad4)") (class "Default")
      (node (ref "X") (pin "4") (pintype "passive"))
    )
    (net (code "174") (name "unconnected-(Y-Pad1)") (class "Default")
      (node (ref "Y") (pin "1") (pintype "passive"))
    )
    (net (code "175") (name "unconnected-(Y-Pad4)") (class "Default")
      (node (ref "Y") (pin "4") (pintype "passive"))
    )
    (net (code "176") (name "unconnected-(Z-Pad1)") (class "Default")
      (node (ref "Z") (pin "1") (pintype "passive"))
    )
    (net (code "177") (name "unconnected-(Z-Pad4)") (class "Default")
      (node (ref "Z") (pin "4") (pintype "passive"))
    )
  )
)
